# mcp3008_rpi_SOIP.net
KiCad netlist of a schematic drawn in EAGLE
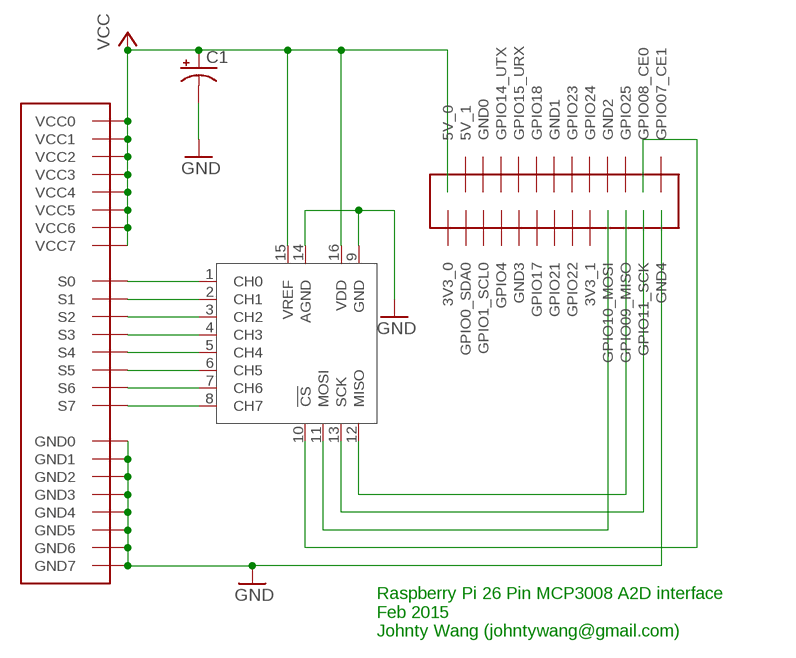
[diagram p0: schematic, sheet 1]

(export (version "E")
  (design (tool "Eeschema 10.0.6"))
  (components
    (comp (ref "C1")
      (value "CPOL-USE2.5-6")
      (footprint "eagle-import:E2,5-6")
      (libsource (lib "eagle-import") (part "CPOL-USE2.5-6"))
    )
    (comp (ref "U$1")
      (value "3BY83X8_SAMTEC")
      (footprint "eagle-import:3X8_PKG")
      (libsource (lib "eagle-import") (part "3BY83X8_SAMTEC"))
    )
    (comp (ref "U$2")
      (value "RPI_26")
      (footprint "eagle-import:RPI26")
      (libsource (lib "eagle-import") (part "RPI_26"))
    )
    (comp (ref "U$3")
      (value "MCP3008SL")
      (footprint "eagle-import:SO16")
      (libsource (lib "eagle-import") (part "MCP3008SL"))
    )
  )
  (nets
    (net (code "1") (name "GND") (class "Default")
      (node (ref "C1") (pin "-") (pinfunction "-_-") (pintype "passive"))
      (node (ref "U$1") (pin "GND0") (pinfunction "GND0_GND0") (pintype "bidirectional"))
      (node (ref "U$1") (pin "GND1") (pinfunction "GND1_GND1") (pintype "bidirectional"))
      (node (ref "U$1") (pin "GND2") (pinfunction "GND2_GND2") (pintype "bidirectional"))
      (node (ref "U$1") (pin "GND3") (pinfunction "GND3_GND3") (pintype "bidirectional"))
      (node (ref "U$1") (pin "GND4") (pinfunction "GND4_GND4") (pintype "bidirectional"))
      (node (ref "U$1") (pin "GND5") (pinfunction "GND5_GND5") (pintype "bidirectional"))
      (node (ref "U$1") (pin "GND6") (pinfunction "GND6_GND6") (pintype "bidirectional"))
      (node (ref "U$1") (pin "GND7") (pinfunction "GND7_GND7") (pintype "bidirectional"))
      (node (ref "U$2") (pin "GND4") (pinfunction "GND4_GND4") (pintype "bidirectional"))
      (node (ref "U$3") (pin "14") (pinfunction "AGND_14") (pintype "power_in"))
      (node (ref "U$3") (pin "9") (pinfunction "GND_9") (pintype "power_in"))
    )
    (net (code "2") (name "Net-(U$2-GPIO08_CE0)") (class "Default")
      (node (ref "U$2") (pin "GPIO08") (pinfunction "GPIO08_CE0_GPIO08") (pintype "bidirectional"))
      (node (ref "U$3") (pin "10") (pinfunction "~{CS}_10") (pintype "input"))
    )
    (net (code "3") (name "Net-(U$2-GPIO09_MISO)") (class "Default")
      (node (ref "U$2") (pin "GPIO09") (pinfunction "GPIO09_MISO_GPIO09") (pintype "bidirectional"))
      (node (ref "U$3") (pin "12") (pinfunction "MISO_12") (pintype "output"))
    )
    (net (code "4") (name "Net-(U$2-GPIO10_MOSI)") (class "Default")
      (node (ref "U$2") (pin "GPIO10") (pinfunction "GPIO10_MOSI_GPIO10") (pintype "bidirectional"))
      (node (ref "U$3") (pin "11") (pinfunction "MOSI_11") (pintype "input"))
    )
    (net (code "5") (name "Net-(U$2-GPIO11_SCK)") (class "Default")
      (node (ref "U$2") (pin "GPIO11") (pinfunction "GPIO11_SCK_GPIO11") (pintype "bidirectional"))
      (node (ref "U$3") (pin "13") (pinfunction "SCK_13") (pintype "input"))
    )
    (net (code "6") (name "Net-(U$3-CH0)") (class "Default")
      (node (ref "U$1") (pin "S0") (pinfunction "S0_S0") (pintype "bidirectional"))
      (node (ref "U$3") (pin "1") (pinfunction "CH0_1") (pintype "input"))
    )
    (net (code "7") (name "Net-(U$3-CH1)") (class "Default")
      (node (ref "U$1") (pin "S1") (pinfunction "S1_S1") (pintype "bidirectional"))
      (node (ref "U$3") (pin "2") (pinfunction "CH1_2") (pintype "input"))
    )
    (net (code "8") (name "Net-(U$3-CH2)") (class "Default")
      (node (ref "U$1") (pin "S2") (pinfunction "S2_S2") (pintype "bidirectional"))
      (node (ref "U$3") (pin "3") (pinfunction "CH2_3") (pintype "input"))
    )
    (net (code "9") (name "Net-(U$3-CH3)") (class "Default")
      (node (ref "U$1") (pin "S3") (pinfunction "S3_S3") (pintype "bidirectional"))
      (node (ref "U$3") (pin "4") (pinfunction "CH3_4") (pintype "input"))
    )
    (net (code "10") (name "Net-(U$3-CH4)") (class "Default")
      (node (ref "U$1") (pin "S4") (pinfunction "S4_S4") (pintype "bidirectional"))
      (node (ref "U$3") (pin "5") (pinfunction "CH4_5") (pintype "input"))
    )
    (net (code "11") (name "Net-(U$3-CH5)") (class "Default")
      (node (ref "U$1") (pin "S5") (pinfunction "S5_S5") (pintype "bidirectional"))
      (node (ref "U$3") (pin "6") (pinfunction "CH5_6") (pintype "input"))
    )
    (net (code "12") (name "Net-(U$3-CH6)") (class "Default")
      (node (ref "U$1") (pin "S6") (pinfunction "S6_S6") (pintype "bidirectional"))
      (node (ref "U$3") (pin "7") (pinfunction "CH6_7") (pintype "input"))
    )
    (net (code "13") (name "Net-(U$3-CH7)") (class "Default")
      (node (ref "U$1") (pin "S7") (pinfunction "S7_S7") (pintype "bidirectional"))
      (node (ref "U$3") (pin "8") (pinfunction "CH7_8") (pintype "input"))
    )
    (net (code "14") (name "VCC") (class "Default")
      (node (ref "C1") (pin "+") (pinfunction "+_+") (pintype "passive"))
      (node (ref "U$1") (pin "VCC0") (pinfunction "VCC0_VCC0") (pintype "bidirectional"))
      (node (ref "U$1") (pin "VCC1") (pinfunction "VCC1_VCC1") (pintype "bidirectional"))
      (node (ref "U$1") (pin "VCC2") (pinfunction "VCC2_VCC2") (pintype "bidirectional"))
      (node (ref "U$1") (pin "VCC3") (pinfunction "VCC3_VCC3") (pintype "bidirectional"))
      (node (ref "U$1") (pin "VCC4") (pinfunction "VCC4_VCC4") (pintype "bidirectional"))
      (node (ref "U$1") (pin "VCC5") (pinfunction "VCC5_VCC5") (pintype "bidirectional"))
      (node (ref "U$1") (pin "VCC6") (pinfunction "VCC6_VCC6") (pintype "bidirectional"))
      (node (ref "U$1") (pin "VCC7") (pinfunction "VCC7_VCC7") (pintype "bidirectional"))
      (node (ref "U$2") (pin "5V0") (pinfunction "5V_0_5V0") (pintype "power_in"))
      (node (ref "U$3") (pin "15") (pinfunction "VREF_15") (pintype "power_in"))
      (node (ref "U$3") (pin "16") (pinfunction "VDD_16") (pintype "power_in"))
    )
    (net (code "15") (name "unconnected-(U$2-5V_1-Pad5V1)") (class "Default")
      (node (ref "U$2") (pin "5V1") (pinfunction "5V_1_5V1") (pintype "bidirectional"))
    )
    (net (code "16") (name "unconnected-(U$2-GPIO0_SDA0-PadGPIO0)") (class "Default")
      (node (ref "U$2") (pin "GPIO0") (pinfunction "GPIO0_SDA0_GPIO0") (pintype "bidirectional"))
    )
    (net (code "17") (name "unconnected-(U$2-GPIO1_SCL0-PadGPIO01)") (class "Default")
      (node (ref "U$2") (pin "GPIO01") (pinfunction "GPIO1_SCL0_GPIO01") (pintype "bidirectional"))
    )
    (net (code "18") (name "unconnected-(U$2-GPIO4-PadGPIO04)") (class "Default")
      (node (ref "U$2") (pin "GPIO04") (pinfunction "GPIO4_GPIO04") (pintype "bidirectional"))
    )
    (net (code "19") (name "unconnected-(U$2-GPIO07_CE1-PadGPIO07)") (class "Default")
      (node (ref "U$2") (pin "GPIO07") (pinfunction "GPIO07_CE1_GPIO07") (pintype "bidirectional"))
    )
    (net (code "20") (name "unconnected-(U$2-GPIO14_UTX-PadGPIO14)") (class "Default")
      (node (ref "U$2") (pin "GPIO14") (pinfunction "GPIO14_UTX_GPIO14") (pintype "bidirectional"))
    )
    (net (code "21") (name "unconnected-(U$2-GPIO15_URX-PadGPIO15)") (class "Default")
      (node (ref "U$2") (pin "GPIO15") (pinfunction "GPIO15_URX_GPIO15") (pintype "bidirectional"))
    )
    (net (code "22") (name "unconnected-(U$2-Pad3V3_0)") (class "Default")
      (node (ref "U$2") (pin "3V3_0") (pinfunction "3V3_0_3V3_0") (pintype "bidirectional"))
    )
    (net (code "23") (name "unconnected-(U$2-Pad3V3_1)") (class "Default")
      (node (ref "U$2") (pin "3V3_1") (pinfunction "3V3_1_3V3_1") (pintype "bidirectional"))
    )
    (net (code "24") (name "unconnected-(U$2-PadGND0)") (class "Default")
      (node (ref "U$2") (pin "GND0") (pinfunction "GND0_GND0") (pintype "bidirectional"))
    )
    (net (code "25") (name "unconnected-(U$2-PadGND1)") (class "Default")
      (node (ref "U$2") (pin "GND1") (pinfunction "GND1_GND1") (pintype "bidirectional"))
    )
    (net (code "26") (name "unconnected-(U$2-PadGND2)") (class "Default")
      (node (ref "U$2") (pin "GND2") (pinfunction "GND2_GND2") (pintype "bidirectional"))
    )
    (net (code "27") (name "unconnected-(U$2-PadGND3)") (class "Default")
      (node (ref "U$2") (pin "GND3") (pinfunction "GND3_GND3") (pintype "bidirectional"))
    )
    (net (code "28") (name "unconnected-(U$2-PadGPIO17)") (class "Default")
      (node (ref "U$2") (pin "GPIO17") (pinfunction "GPIO17_GPIO17") (pintype "bidirectional"))
    )
    (net (code "29") (name "unconnected-(U$2-PadGPIO18)") (class "Default")
      (node (ref "U$2") (pin "GPIO18") (pinfunction "GPIO18_GPIO18") (pintype "bidirectional"))
    )
    (net (code "30") (name "unconnected-(U$2-PadGPIO21)") (class "Default")
      (node (ref "U$2") (pin "GPIO21") (pinfunction "GPIO21_GPIO21") (pintype "bidirectional"))
    )
    (net (code "31") (name "unconnected-(U$2-PadGPIO22)") (class "Default")
      (node (ref "U$2") (pin "GPIO22") (pinfunction "GPIO22_GPIO22") (pintype "bidirectional"))
    )
    (net (code "32") (name "unconnected-(U$2-PadGPIO23)") (class "Default")
      (node (ref "U$2") (pin "GPIO23") (pinfunction "GPIO23_GPIO23") (pintype "bidirectional"))
    )
    (net (code "33") (name "unconnected-(U$2-PadGPIO24)") (class "Default")
      (node (ref "U$2") (pin "GPIO24") (pinfunction "GPIO24_GPIO24") (pintype "bidirectional"))
    )
    (net (code "34") (name "unconnected-(U$2-PadGPIO25)") (class "Default")
      (node (ref "U$2") (pin "GPIO25") (pinfunction "GPIO25_GPIO25") (pintype "bidirectional"))
    )
  )
)
